# switch-smd-20mm-mk-2_0.net
KiCad netlist of a schematic drawn in EAGLE
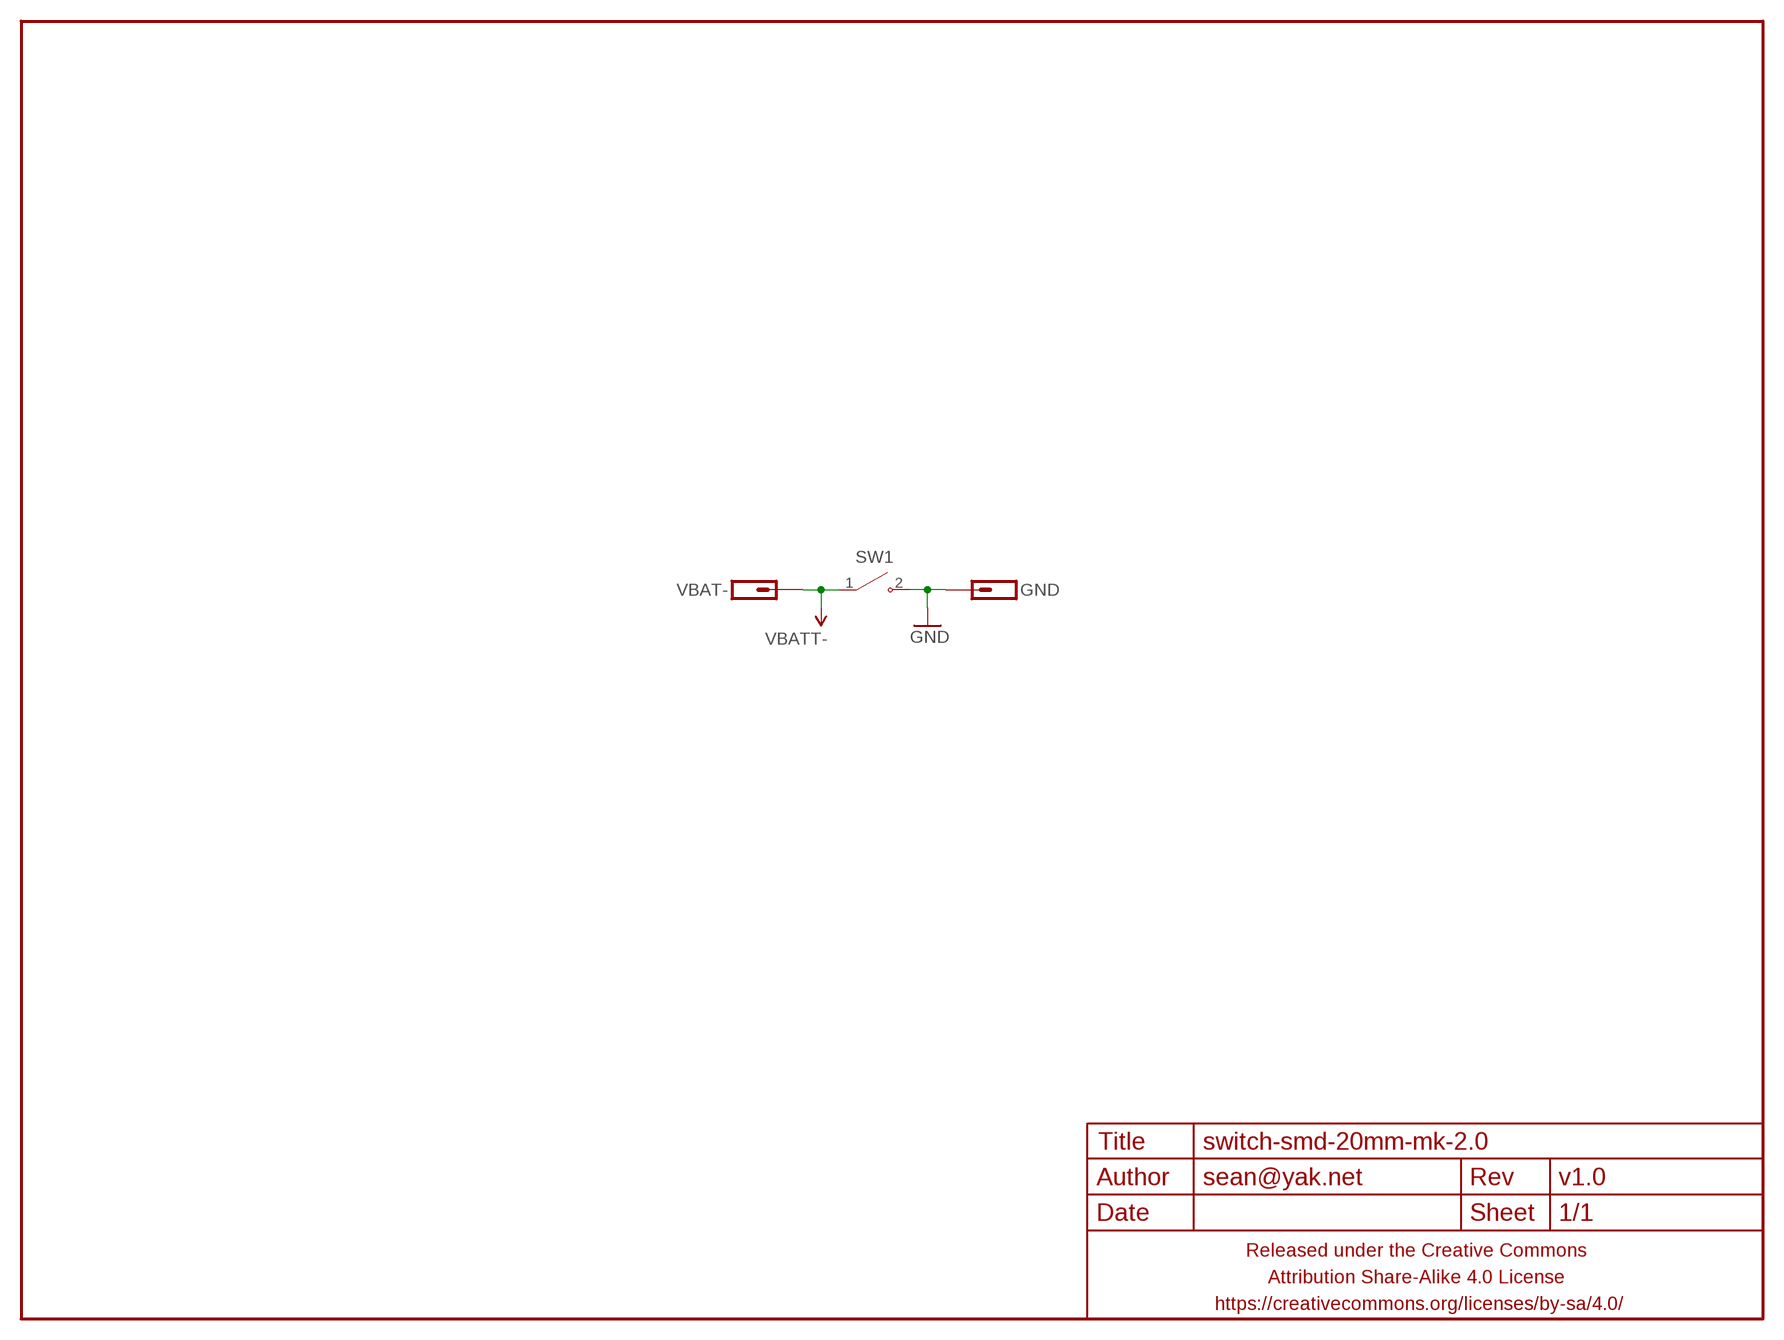
[diagram p0: schematic, sheet 1]

(export (version "E")
  (design (tool "Eeschema 10.0.6"))
  (components
    (comp (ref "FRAME1")
      (value "FRAME-LETTERNO_PACKAGE")
      (footprint "eagle-import:DUMMY")
      (fields (field (name "DESIGNER") "sean@yak.net") (field (name "VERSION") "v1.0"))
      (libsource (lib "eagle-import") (part "FRAME-LETTERNO_PACKAGE"))
    )
    (comp (ref "GND")
      (value "M01NOT-A-VIA-NOPE")
      (footprint "eagle-import:1X01_NOSILK_NOSTOP")
      (libsource (lib "eagle-import") (part "M01NOT-A-VIA-NOPE"))
    )
    (comp (ref "SW1")
      (value "SWITCH-SPSTKAN-9-SMD-SMOL-TWO-SIDES")
      (footprint "eagle-import:KAN-9-SMD-SMOL-TWO-SIDES")
      (libsource (lib "eagle-import") (part "SWITCH-SPSTKAN-9-SMD-SMOL-TWO-SIDES"))
    )
    (comp (ref "VBAT-")
      (value "M01PTH-1MM-CIR-NS")
      (footprint "eagle-import:1X01-1MM-CIR-NS")
      (libsource (lib "eagle-import") (part "M01PTH-1MM-CIR-NS"))
    )
  )
  (nets
    (net (code "1") (name "GND") (class "Default")
      (node (ref "GND") (pin "P$1") (pinfunction "1_P$1") (pintype "passive"))
      (node (ref "SW1") (pin "2") (pinfunction "NO_2") (pintype "bidirectional"))
    )
    (net (code "2") (name "VBATT-") (class "Default")
      (node (ref "SW1") (pin "1") (pinfunction "COM_1") (pintype "bidirectional"))
      (node (ref "VBAT-") (pin "1") (pinfunction "1_1") (pintype "passive"))
    )
  )
)
